# DCDC-5VXV3A.net
KiCad netlist of a schematic drawn in EAGLE
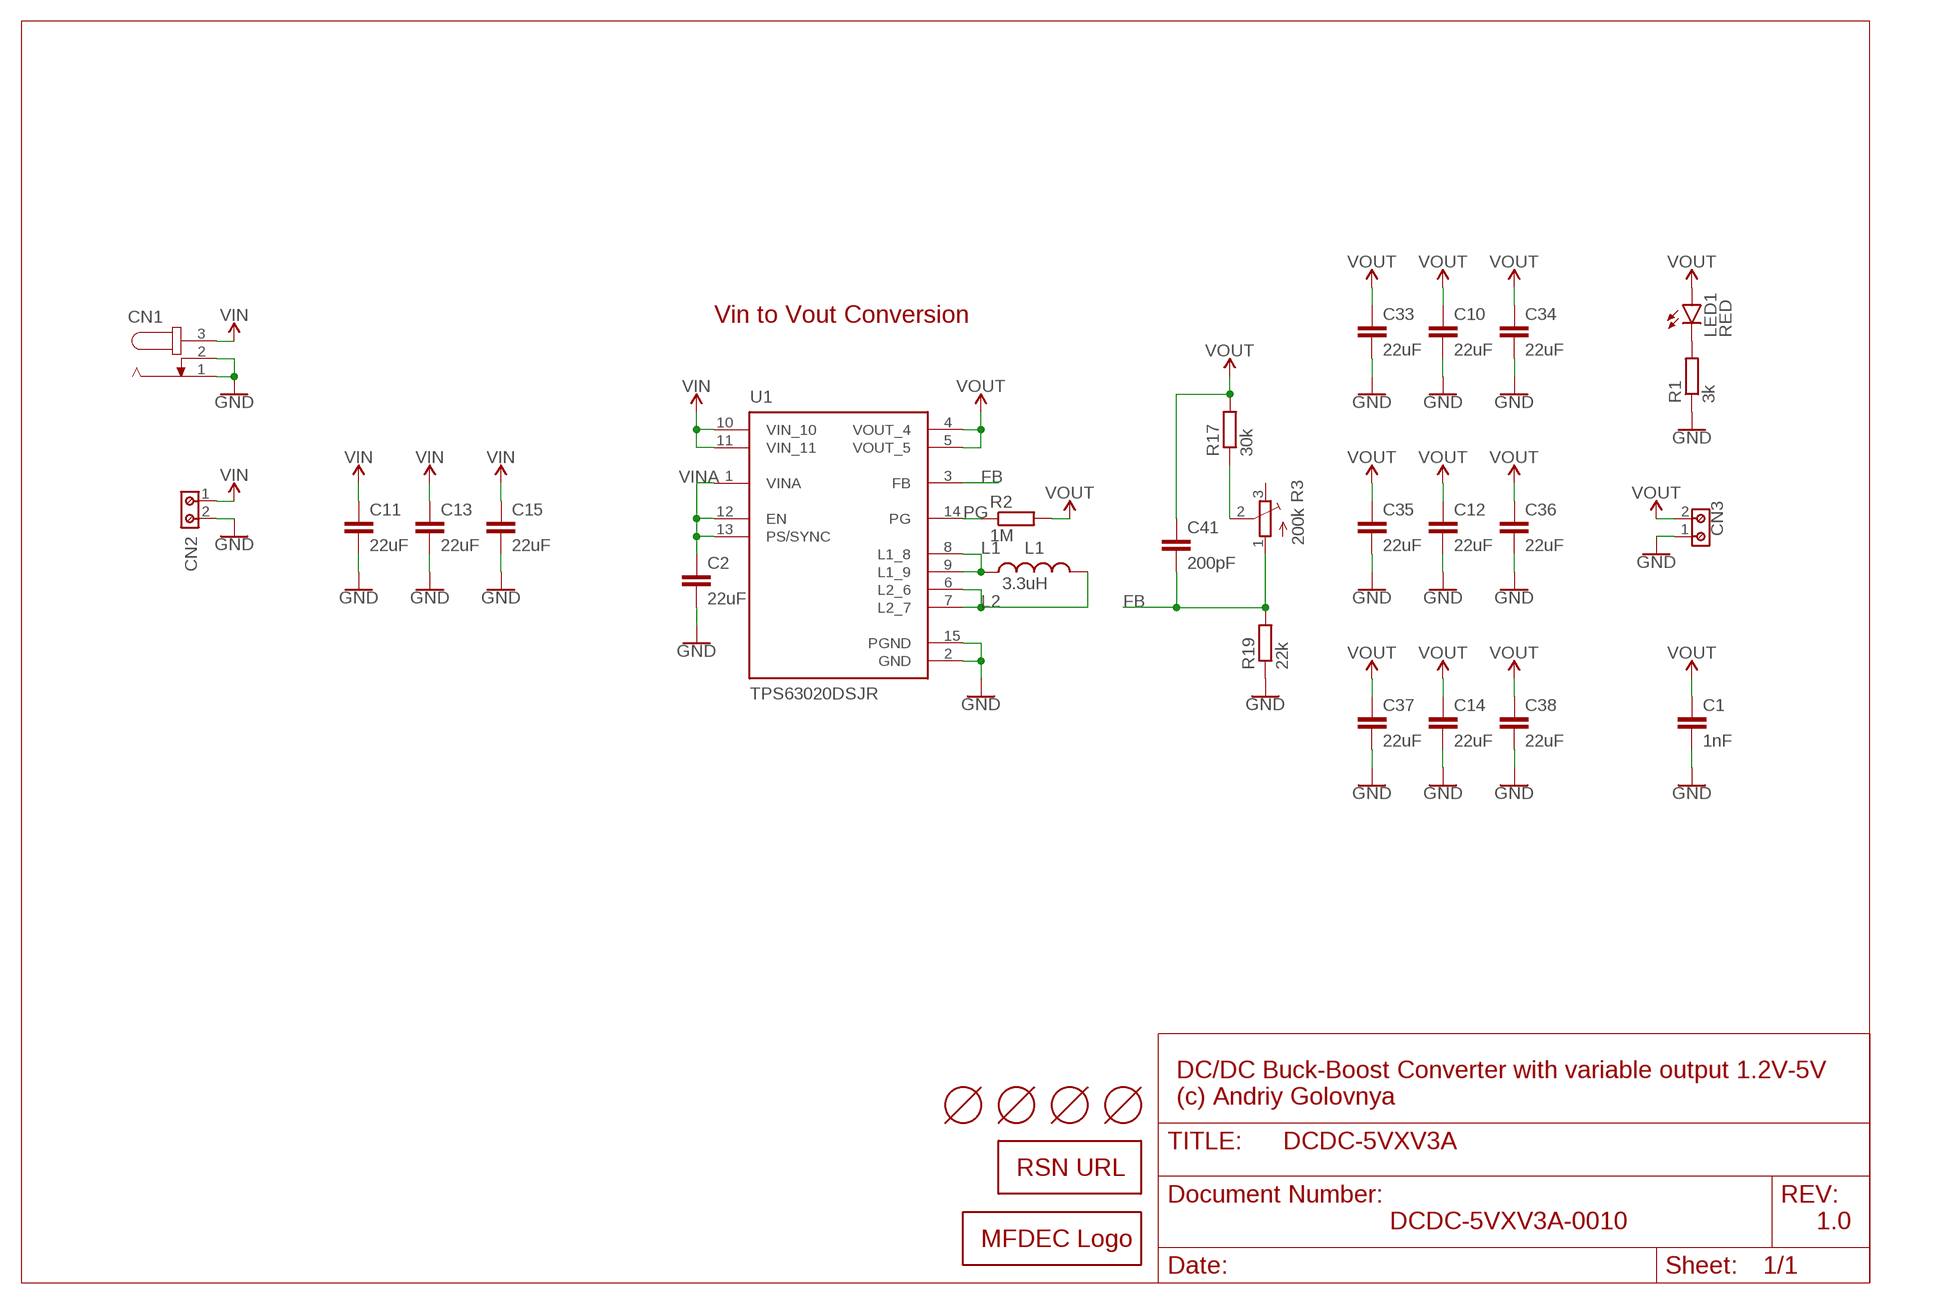
[diagram p0: schematic, sheet 1]

(export (version "E")
  (design (tool "Eeschema 10.0.6"))
  (components
    (comp (ref "C1")
      (value "1nF")
      (footprint "eagle-import:C0603K")
      (libsource (lib "eagle-import") (part "C-EUC0603K"))
    )
    (comp (ref "C2")
      (value "22uF")
      (footprint "eagle-import:C0805K")
      (libsource (lib "eagle-import") (part "C-EUC0805K"))
    )
    (comp (ref "C10")
      (value "22uF")
      (footprint "eagle-import:C0805K")
      (libsource (lib "eagle-import") (part "C-EUC0805K"))
    )
    (comp (ref "C11")
      (value "22uF")
      (footprint "eagle-import:C0805K")
      (libsource (lib "eagle-import") (part "C-EUC0805K"))
    )
    (comp (ref "C12")
      (value "22uF")
      (footprint "eagle-import:C0805K")
      (libsource (lib "eagle-import") (part "C-EUC0805K"))
    )
    (comp (ref "C13")
      (value "22uF")
      (footprint "eagle-import:C0805K")
      (libsource (lib "eagle-import") (part "C-EUC0805K"))
    )
    (comp (ref "C14")
      (value "22uF")
      (footprint "eagle-import:C0805K")
      (libsource (lib "eagle-import") (part "C-EUC0805K"))
    )
    (comp (ref "C15")
      (value "22uF")
      (footprint "eagle-import:C0805K")
      (libsource (lib "eagle-import") (part "C-EUC0805K"))
    )
    (comp (ref "C33")
      (value "22uF")
      (footprint "eagle-import:C0805K")
      (libsource (lib "eagle-import") (part "C-EUC0805K"))
    )
    (comp (ref "C34")
      (value "22uF")
      (footprint "eagle-import:C0805K")
      (libsource (lib "eagle-import") (part "C-EUC0805K"))
    )
    (comp (ref "C35")
      (value "22uF")
      (footprint "eagle-import:C0805K")
      (libsource (lib "eagle-import") (part "C-EUC0805K"))
    )
    (comp (ref "C36")
      (value "22uF")
      (footprint "eagle-import:C0805K")
      (libsource (lib "eagle-import") (part "C-EUC0805K"))
    )
    (comp (ref "C37")
      (value "22uF")
      (footprint "eagle-import:C0805K")
      (libsource (lib "eagle-import") (part "C-EUC0805K"))
    )
    (comp (ref "C38")
      (value "22uF")
      (footprint "eagle-import:C0805K")
      (libsource (lib "eagle-import") (part "C-EUC0805K"))
    )
    (comp (ref "C41")
      (value "200pF")
      (footprint "eagle-import:C0603K")
      (libsource (lib "eagle-import") (part "C-EUC0603K"))
    )
    (comp (ref "CN1")
      (value "JACK-PLUG1")
      (footprint "eagle-import:SPC4078")
      (libsource (lib "eagle-import") (part "JACK-PLUG1"))
    )
    (comp (ref "CN2")
      (value "691213510002")
      (footprint "eagle-import:691213510002")
      (libsource (lib "eagle-import") (part "691213510002"))
    )
    (comp (ref "CN3")
      (value "691213510002")
      (footprint "eagle-import:691213510002")
      (libsource (lib "eagle-import") (part "691213510002"))
    )
    (comp (ref "HOLE1")
      (value "TOOLINGHOLE")
      (footprint "eagle-import:TOOLING-HOLE")
      (libsource (lib "eagle-import") (part "TOOLINGHOLE"))
    )
    (comp (ref "HOLE2")
      (value "TOOLINGHOLE")
      (footprint "eagle-import:TOOLING-HOLE")
      (libsource (lib "eagle-import") (part "TOOLINGHOLE"))
    )
    (comp (ref "HOLE3")
      (value "TOOLINGHOLE")
      (footprint "eagle-import:TOOLING-HOLE")
      (libsource (lib "eagle-import") (part "TOOLINGHOLE"))
    )
    (comp (ref "HOLE4")
      (value "TOOLINGHOLE")
      (footprint "eagle-import:TOOLING-HOLE")
      (libsource (lib "eagle-import") (part "TOOLINGHOLE"))
    )
    (comp (ref "L1")
      (value "3.3uH")
      (footprint "eagle-import:WE-CHSA_1011")
      (libsource (lib "eagle-import") (part "WE-CHSA_1011_7843330330"))
    )
    (comp (ref "LED1")
      (value "RED")
      (footprint "eagle-import:SML0603")
      (libsource (lib "eagle-import") (part "LEDSML0603"))
    )
    (comp (ref "LOGO1")
      (value "RSNURL_QR_8MM")
      (footprint "eagle-import:RSNURL_QR_8MM")
      (libsource (lib "eagle-import") (part "RSNURL_QR_8MM"))
    )
    (comp (ref "LOGO2")
      (value "MFDECLOGO_L_10MM")
      (footprint "eagle-import:MFDEC_L_10MM")
      (libsource (lib "eagle-import") (part "MFDECLOGO_L_10MM"))
    )
    (comp (ref "R1")
      (value "3k")
      (footprint "eagle-import:R0603")
      (libsource (lib "eagle-import") (part "R-EU_R0603"))
    )
    (comp (ref "R2")
      (value "1M")
      (footprint "eagle-import:R0603")
      (libsource (lib "eagle-import") (part "R-EU_R0603"))
    )
    (comp (ref "R3")
      (value "200k")
      (footprint "eagle-import:TC33X")
      (libsource (lib "eagle-import") (part "TRIMPOTTC33X"))
    )
    (comp (ref "R17")
      (value "30k")
      (footprint "eagle-import:R0603")
      (libsource (lib "eagle-import") (part "R-EU_R0603"))
    )
    (comp (ref "R19")
      (value "22k")
      (footprint "eagle-import:R0603")
      (libsource (lib "eagle-import") (part "R-EU_R0603"))
    )
    (comp (ref "U1")
      (value "TPS63020DSJR")
      (footprint "eagle-import:IC_TPS63020DSJR")
      (fields (field (name "MF") "Texas Instruments"))
      (libsource (lib "eagle-import") (part "TPS63020DSJR"))
    )
  )
  (nets
    (net (code "1") (name "/FB") (class "Default")
      (node (ref "C41") (pin "2") (pinfunction "2_2") (pintype "passive"))
      (node (ref "R19") (pin "2") (pinfunction "2_2") (pintype "passive"))
      (node (ref "R3") (pin "1") (pinfunction "A_1") (pintype "passive"))
      (node (ref "U1") (pin "3") (pinfunction "FB_3") (pintype "input"))
    )
    (net (code "2") (name "/L1") (class "Default")
      (node (ref "L1") (pin "1") (pinfunction "1_1") (pintype "passive"))
      (node (ref "U1") (pin "8") (pinfunction "L1_8_8") (pintype "passive"))
      (node (ref "U1") (pin "9") (pinfunction "L1_9_9") (pintype "passive"))
    )
    (net (code "3") (name "/L2") (class "Default")
      (node (ref "L1") (pin "2") (pinfunction "2_2") (pintype "passive"))
      (node (ref "U1") (pin "6") (pinfunction "L2_6_6") (pintype "passive"))
      (node (ref "U1") (pin "7") (pinfunction "L2_7_7") (pintype "passive"))
    )
    (net (code "4") (name "/PG") (class "Default")
      (node (ref "R2") (pin "1") (pinfunction "1_1") (pintype "passive"))
      (node (ref "U1") (pin "14") (pinfunction "PG_14") (pintype "output"))
    )
    (net (code "5") (name "/VINA") (class "Default")
      (node (ref "C2") (pin "1") (pinfunction "1_1") (pintype "passive"))
      (node (ref "U1") (pin "1") (pinfunction "VINA_1") (pintype "input"))
      (node (ref "U1") (pin "12") (pinfunction "EN_12") (pintype "input"))
      (node (ref "U1") (pin "13") (pinfunction "PS/SYNC_13") (pintype "input"))
    )
    (net (code "6") (name "GND") (class "Default")
      (node (ref "C1") (pin "2") (pinfunction "2_2") (pintype "passive"))
      (node (ref "C10") (pin "2") (pinfunction "2_2") (pintype "passive"))
      (node (ref "C11") (pin "2") (pinfunction "2_2") (pintype "passive"))
      (node (ref "C12") (pin "2") (pinfunction "2_2") (pintype "passive"))
      (node (ref "C13") (pin "2") (pinfunction "2_2") (pintype "passive"))
      (node (ref "C14") (pin "2") (pinfunction "2_2") (pintype "passive"))
      (node (ref "C15") (pin "2") (pinfunction "2_2") (pintype "passive"))
      (node (ref "C2") (pin "2") (pinfunction "2_2") (pintype "passive"))
      (node (ref "C33") (pin "2") (pinfunction "2_2") (pintype "passive"))
      (node (ref "C34") (pin "2") (pinfunction "2_2") (pintype "passive"))
      (node (ref "C35") (pin "2") (pinfunction "2_2") (pintype "passive"))
      (node (ref "C36") (pin "2") (pinfunction "2_2") (pintype "passive"))
      (node (ref "C37") (pin "2") (pinfunction "2_2") (pintype "passive"))
      (node (ref "C38") (pin "2") (pinfunction "2_2") (pintype "passive"))
      (node (ref "CN1") (pin "1") (pinfunction "1_1") (pintype "passive"))
      (node (ref "CN1") (pin "2") (pinfunction "2_2") (pintype "passive"))
      (node (ref "CN2") (pin "2") (pinfunction "2_2") (pintype "passive"))
      (node (ref "CN3") (pin "1") (pinfunction "1_1") (pintype "passive"))
      (node (ref "R1") (pin "1") (pinfunction "1_1") (pintype "passive"))
      (node (ref "R19") (pin "1") (pinfunction "1_1") (pintype "passive"))
      (node (ref "U1") (pin "15") (pinfunction "PGND_15") (pintype "power_in"))
      (node (ref "U1") (pin "2") (pinfunction "GND_2") (pintype "power_in"))
    )
    (net (code "7") (name "Net-(LED1-PadC)") (class "Default")
      (node (ref "LED1") (pin "C") (pinfunction "C_C") (pintype "passive"))
      (node (ref "R1") (pin "2") (pinfunction "2_2") (pintype "passive"))
    )
    (net (code "8") (name "Net-(R3-S)") (class "Default")
      (node (ref "R17") (pin "1") (pinfunction "1_1") (pintype "passive"))
      (node (ref "R3") (pin "2") (pinfunction "S_2") (pintype "passive"))
    )
    (net (code "9") (name "VIN") (class "Default")
      (node (ref "C11") (pin "1") (pinfunction "1_1") (pintype "passive"))
      (node (ref "C13") (pin "1") (pinfunction "1_1") (pintype "passive"))
      (node (ref "C15") (pin "1") (pinfunction "1_1") (pintype "passive"))
      (node (ref "CN1") (pin "3") (pinfunction "3_3") (pintype "passive"))
      (node (ref "CN2") (pin "1") (pinfunction "1_1") (pintype "passive"))
      (node (ref "U1") (pin "10") (pinfunction "VIN_10_10") (pintype "input"))
      (node (ref "U1") (pin "11") (pinfunction "VIN_11_11") (pintype "input"))
    )
    (net (code "10") (name "VOUT") (class "Default")
      (node (ref "C1") (pin "1") (pinfunction "1_1") (pintype "passive"))
      (node (ref "C10") (pin "1") (pinfunction "1_1") (pintype "passive"))
      (node (ref "C12") (pin "1") (pinfunction "1_1") (pintype "passive"))
      (node (ref "C14") (pin "1") (pinfunction "1_1") (pintype "passive"))
      (node (ref "C33") (pin "1") (pinfunction "1_1") (pintype "passive"))
      (node (ref "C34") (pin "1") (pinfunction "1_1") (pintype "passive"))
      (node (ref "C35") (pin "1") (pinfunction "1_1") (pintype "passive"))
      (node (ref "C36") (pin "1") (pinfunction "1_1") (pintype "passive"))
      (node (ref "C37") (pin "1") (pinfunction "1_1") (pintype "passive"))
      (node (ref "C38") (pin "1") (pinfunction "1_1") (pintype "passive"))
      (node (ref "C41") (pin "1") (pinfunction "1_1") (pintype "passive"))
      (node (ref "CN3") (pin "2") (pinfunction "2_2") (pintype "passive"))
      (node (ref "LED1") (pin "A") (pinfunction "A_A") (pintype "passive"))
      (node (ref "R17") (pin "2") (pinfunction "2_2") (pintype "passive"))
      (node (ref "R2") (pin "2") (pinfunction "2_2") (pintype "passive"))
      (node (ref "U1") (pin "4") (pinfunction "VOUT_4_4") (pintype "output"))
      (node (ref "U1") (pin "5") (pinfunction "VOUT_5_5") (pintype "output"))
    )
    (net (code "11") (name "unconnected-(R3-E-Pad3)") (class "Default")
      (node (ref "R3") (pin "3") (pinfunction "E_3") (pintype "passive"))
    )
  )
)
